# CAN_Transceiver.net
KiCad netlist of a schematic drawn in Altium Designer
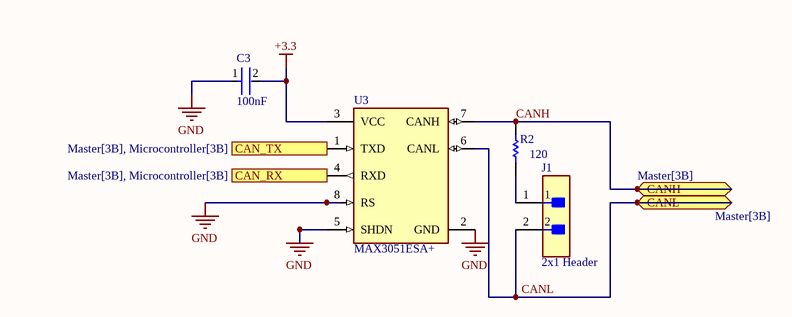
[diagram p0: CAN_Transceiver.SchDoc]

(export (version "E")
  (design (tool "Eeschema 10.0.6"))
  (components
    (comp (ref "C3")
      (value "100nF")
      (footprint "CAPC0603(1608)100_L")
      (description "GENERIC CAPACITOR 0805 or 0603(1608)")
      (libsource (lib "Sooner Competitive Robotics") (part "11868f565c42a9108669ba33697ecf6"))
    )
    (comp (ref "J1")
      (value "2x1 Header")
      (footprint "0.1\" Header 2x1-Footprint")
      (libsource (lib "Sooner Competitive Robotics") (part "3bc925449376181038e59eaffc5286c"))
    )
    (comp (ref "R2")
      (value "120")
      (footprint "RESC2013X50X30ML20T20")
      (description "Surface Mount 0805 Resistor")
      (libsource (lib "Sooner Competitive Robotics") (part "RES"))
    )
    (comp (ref "U3")
      (value "MAX3051ESA+")
      (footprint "FP-S8-4-IPC_B")
      (description "MAX3051 Series 3.3 V 1 Mbps Low-Supply-Current CAN Transceiver - SOIC-8")
      (libsource (lib "Sooner Competitive Robotics") (part "de9644a7d726ac8b5141fed6c40124c"))
    )
  )
  (nets
    (net (code "1") (name "+3.3") (class "Default")
      (node (ref "C3") (pin "2") (pinfunction "2_2") (pintype "passive"))
      (node (ref "U3") (pin "3") (pinfunction "VCC_3") (pintype "power_in"))
    )
    (net (code "2") (name "/CANH") (class "Default")
      (node (ref "R2") (pin "2") (pinfunction "2_2") (pintype "passive"))
      (node (ref "U3") (pin "7") (pinfunction "CANH_7") (pintype "bidirectional"))
    )
    (net (code "3") (name "/CANL") (class "Default")
      (node (ref "J1") (pin "2") (pinfunction "2_2") (pintype "passive"))
      (node (ref "U3") (pin "6") (pinfunction "CANL_6") (pintype "bidirectional"))
    )
    (net (code "4") (name "/CAN_RX") (class "Default")
      (node (ref "U3") (pin "4") (pinfunction "RXD_4") (pintype "output"))
    )
    (net (code "5") (name "/CAN_TX") (class "Default")
      (node (ref "U3") (pin "1") (pinfunction "TXD_1") (pintype "input"))
    )
    (net (code "6") (name "GND") (class "Default")
      (node (ref "C3") (pin "1") (pinfunction "1_1") (pintype "passive"))
      (node (ref "U3") (pin "2") (pinfunction "GND_2") (pintype "power_in"))
      (node (ref "U3") (pin "5") (pinfunction "SHDN_5") (pintype "input"))
      (node (ref "U3") (pin "8") (pinfunction "RS_8") (pintype "input"))
    )
    (net (code "7") (name "Net-(J1-Pad1)") (class "Default")
      (node (ref "J1") (pin "1") (pinfunction "1_1") (pintype "passive"))
      (node (ref "R2") (pin "1") (pinfunction "1_1") (pintype "passive"))
    )
  )
)
